# 7-segment.net
KiCad netlist of a schematic drawn in EAGLE
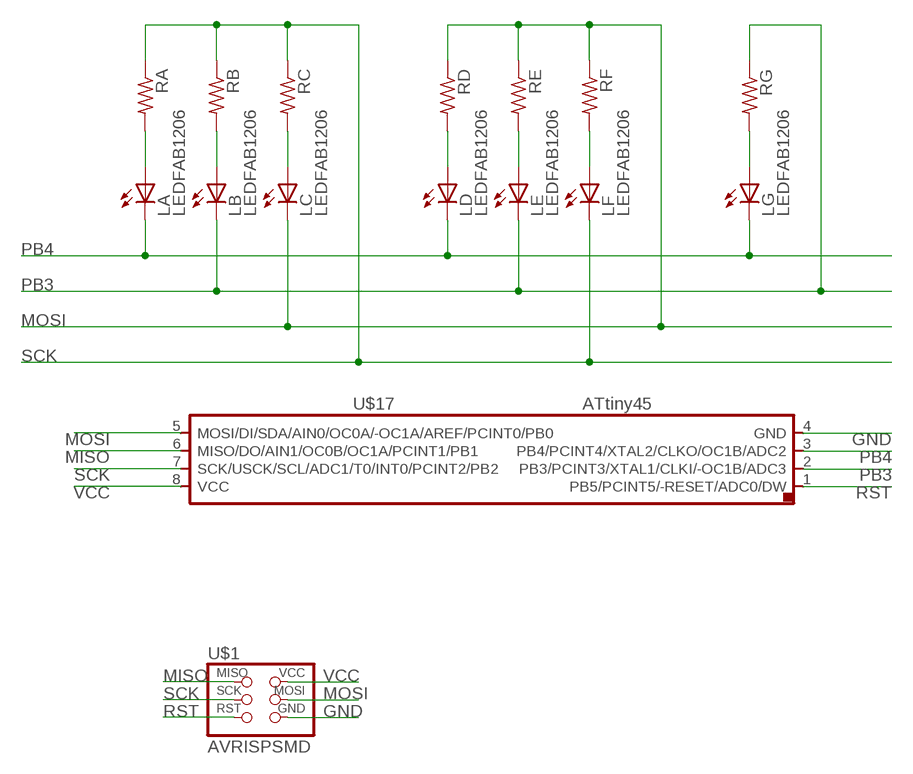
[diagram p0: schematic, sheet 1]

(export (version "E")
  (design (tool "Eeschema 10.0.6"))
  (components
    (comp (ref "LA")
      (value "LEDFAB1206")
      (footprint "eagle-import:LED1206FAB")
      (libsource (lib "eagle-import") (part "LEDFAB1206"))
    )
    (comp (ref "LB")
      (value "LEDFAB1206")
      (footprint "eagle-import:LED1206FAB")
      (libsource (lib "eagle-import") (part "LEDFAB1206"))
    )
    (comp (ref "LC")
      (value "LEDFAB1206")
      (footprint "eagle-import:LED1206FAB")
      (libsource (lib "eagle-import") (part "LEDFAB1206"))
    )
    (comp (ref "LD")
      (value "LEDFAB1206")
      (footprint "eagle-import:LED1206FAB")
      (libsource (lib "eagle-import") (part "LEDFAB1206"))
    )
    (comp (ref "LE")
      (value "LEDFAB1206")
      (footprint "eagle-import:LED1206FAB")
      (libsource (lib "eagle-import") (part "LEDFAB1206"))
    )
    (comp (ref "LF")
      (value "LEDFAB1206")
      (footprint "eagle-import:LED1206FAB")
      (libsource (lib "eagle-import") (part "LEDFAB1206"))
    )
    (comp (ref "LG")
      (value "LEDFAB1206")
      (footprint "eagle-import:LED1206FAB")
      (libsource (lib "eagle-import") (part "LEDFAB1206"))
    )
    (comp (ref "RA")
      (value "RES-US1206FAB")
      (footprint "eagle-import:R1206FAB")
      (libsource (lib "eagle-import") (part "RES-US1206FAB"))
    )
    (comp (ref "RB")
      (value "RES-US1206FAB")
      (footprint "eagle-import:R1206FAB")
      (libsource (lib "eagle-import") (part "RES-US1206FAB"))
    )
    (comp (ref "RC")
      (value "RES-US1206FAB")
      (footprint "eagle-import:R1206FAB")
      (libsource (lib "eagle-import") (part "RES-US1206FAB"))
    )
    (comp (ref "RD")
      (value "RES-US1206FAB")
      (footprint "eagle-import:R1206FAB")
      (libsource (lib "eagle-import") (part "RES-US1206FAB"))
    )
    (comp (ref "RE")
      (value "RES-US1206FAB")
      (footprint "eagle-import:R1206FAB")
      (libsource (lib "eagle-import") (part "RES-US1206FAB"))
    )
    (comp (ref "RF")
      (value "RES-US1206FAB")
      (footprint "eagle-import:R1206FAB")
      (libsource (lib "eagle-import") (part "RES-US1206FAB"))
    )
    (comp (ref "RG")
      (value "RES-US1206FAB")
      (footprint "eagle-import:R1206FAB")
      (libsource (lib "eagle-import") (part "RES-US1206FAB"))
    )
    (comp (ref "U$1")
      (value "AVRISPSMD")
      (footprint "eagle-import:2X03SMD")
      (libsource (lib "eagle-import") (part "AVRISPSMD"))
    )
    (comp (ref "U$17")
      (value "ATTINY45SI")
      (footprint "eagle-import:SOIC8")
      (libsource (lib "eagle-import") (part "ATTINY45SI"))
    )
  )
  (nets
    (net (code "1") (name "/GND") (class "Default")
      (node (ref "U$1") (pin "6") (pinfunction "GND_6") (pintype "passive"))
      (node (ref "U$17") (pin "4") (pinfunction "GND_4") (pintype "bidirectional"))
    )
    (net (code "2") (name "/MISO") (class "Default")
      (node (ref "U$1") (pin "1") (pinfunction "MISO_1") (pintype "passive"))
      (node (ref "U$17") (pin "6") (pinfunction "MISO/DO/AIN1/OC0B/OC1A/PCINT1/PB1_6") (pintype "bidirectional"))
    )
    (net (code "3") (name "/MOSI") (class "Default")
      (node (ref "LC") (pin "2") (pinfunction "C_2") (pintype "passive"))
      (node (ref "RD") (pin "1") (pinfunction "1_1") (pintype "passive"))
      (node (ref "RE") (pin "1") (pinfunction "1_1") (pintype "passive"))
      (node (ref "RF") (pin "1") (pinfunction "1_1") (pintype "passive"))
      (node (ref "U$1") (pin "4") (pinfunction "MOSI_4") (pintype "passive"))
      (node (ref "U$17") (pin "5") (pinfunction "MOSI/DI/SDA/AIN0/OC0A/-OC1A/AREF/PCINT0/PB0_5") (pintype "bidirectional"))
    )
    (net (code "4") (name "/PB3") (class "Default")
      (node (ref "LB") (pin "2") (pinfunction "C_2") (pintype "passive"))
      (node (ref "LE") (pin "2") (pinfunction "C_2") (pintype "passive"))
      (node (ref "RG") (pin "1") (pinfunction "1_1") (pintype "passive"))
      (node (ref "U$17") (pin "2") (pinfunction "PB3/PCINT3/XTAL1/CLKI/-OC1B/ADC3_2") (pintype "bidirectional"))
    )
    (net (code "5") (name "/PB4") (class "Default")
      (node (ref "LA") (pin "2") (pinfunction "C_2") (pintype "passive"))
      (node (ref "LD") (pin "2") (pinfunction "C_2") (pintype "passive"))
      (node (ref "LG") (pin "2") (pinfunction "C_2") (pintype "passive"))
      (node (ref "U$17") (pin "3") (pinfunction "PB4/PCINT4/XTAL2/CLKO/OC1B/ADC2_3") (pintype "bidirectional"))
    )
    (net (code "6") (name "/RST") (class "Default")
      (node (ref "U$1") (pin "5") (pinfunction "RST_5") (pintype "passive"))
      (node (ref "U$17") (pin "1") (pinfunction "PB5/PCINT5/-RESET/ADC0/DW_1") (pintype "bidirectional"))
    )
    (net (code "7") (name "/SCK") (class "Default")
      (node (ref "LF") (pin "2") (pinfunction "C_2") (pintype "passive"))
      (node (ref "RA") (pin "1") (pinfunction "1_1") (pintype "passive"))
      (node (ref "RB") (pin "1") (pinfunction "1_1") (pintype "passive"))
      (node (ref "RC") (pin "1") (pinfunction "1_1") (pintype "passive"))
      (node (ref "U$1") (pin "3") (pinfunction "SCK_3") (pintype "passive"))
      (node (ref "U$17") (pin "7") (pinfunction "SCK/USCK/SCL/ADC1/T0/INT0/PCINT2/PB2_7") (pintype "bidirectional"))
    )
    (net (code "8") (name "/VCC") (class "Default")
      (node (ref "U$1") (pin "2") (pinfunction "VCC_2") (pintype "passive"))
      (node (ref "U$17") (pin "8") (pinfunction "VCC_8") (pintype "bidirectional"))
    )
    (net (code "9") (name "Net-(LA-A)") (class "Default")
      (node (ref "LA") (pin "1") (pinfunction "A_1") (pintype "passive"))
      (node (ref "RA") (pin "2") (pinfunction "2_2") (pintype "passive"))
    )
    (net (code "10") (name "Net-(LB-A)") (class "Default")
      (node (ref "LB") (pin "1") (pinfunction "A_1") (pintype "passive"))
      (node (ref "RB") (pin "2") (pinfunction "2_2") (pintype "passive"))
    )
    (net (code "11") (name "Net-(LC-A)") (class "Default")
      (node (ref "LC") (pin "1") (pinfunction "A_1") (pintype "passive"))
      (node (ref "RC") (pin "2") (pinfunction "2_2") (pintype "passive"))
    )
    (net (code "12") (name "Net-(LD-A)") (class "Default")
      (node (ref "LD") (pin "1") (pinfunction "A_1") (pintype "passive"))
      (node (ref "RD") (pin "2") (pinfunction "2_2") (pintype "passive"))
    )
    (net (code "13") (name "Net-(LE-A)") (class "Default")
      (node (ref "LE") (pin "1") (pinfunction "A_1") (pintype "passive"))
      (node (ref "RE") (pin "2") (pinfunction "2_2") (pintype "passive"))
    )
    (net (code "14") (name "Net-(LF-A)") (class "Default")
      (node (ref "LF") (pin "1") (pinfunction "A_1") (pintype "passive"))
      (node (ref "RF") (pin "2") (pinfunction "2_2") (pintype "passive"))
    )
    (net (code "15") (name "Net-(LG-A)") (class "Default")
      (node (ref "LG") (pin "1") (pinfunction "A_1") (pintype "passive"))
      (node (ref "RG") (pin "2") (pinfunction "2_2") (pintype "passive"))
    )
  )
)
